# Mega_Stepper_Shield.net
KiCad netlist of a schematic drawn in EAGLE
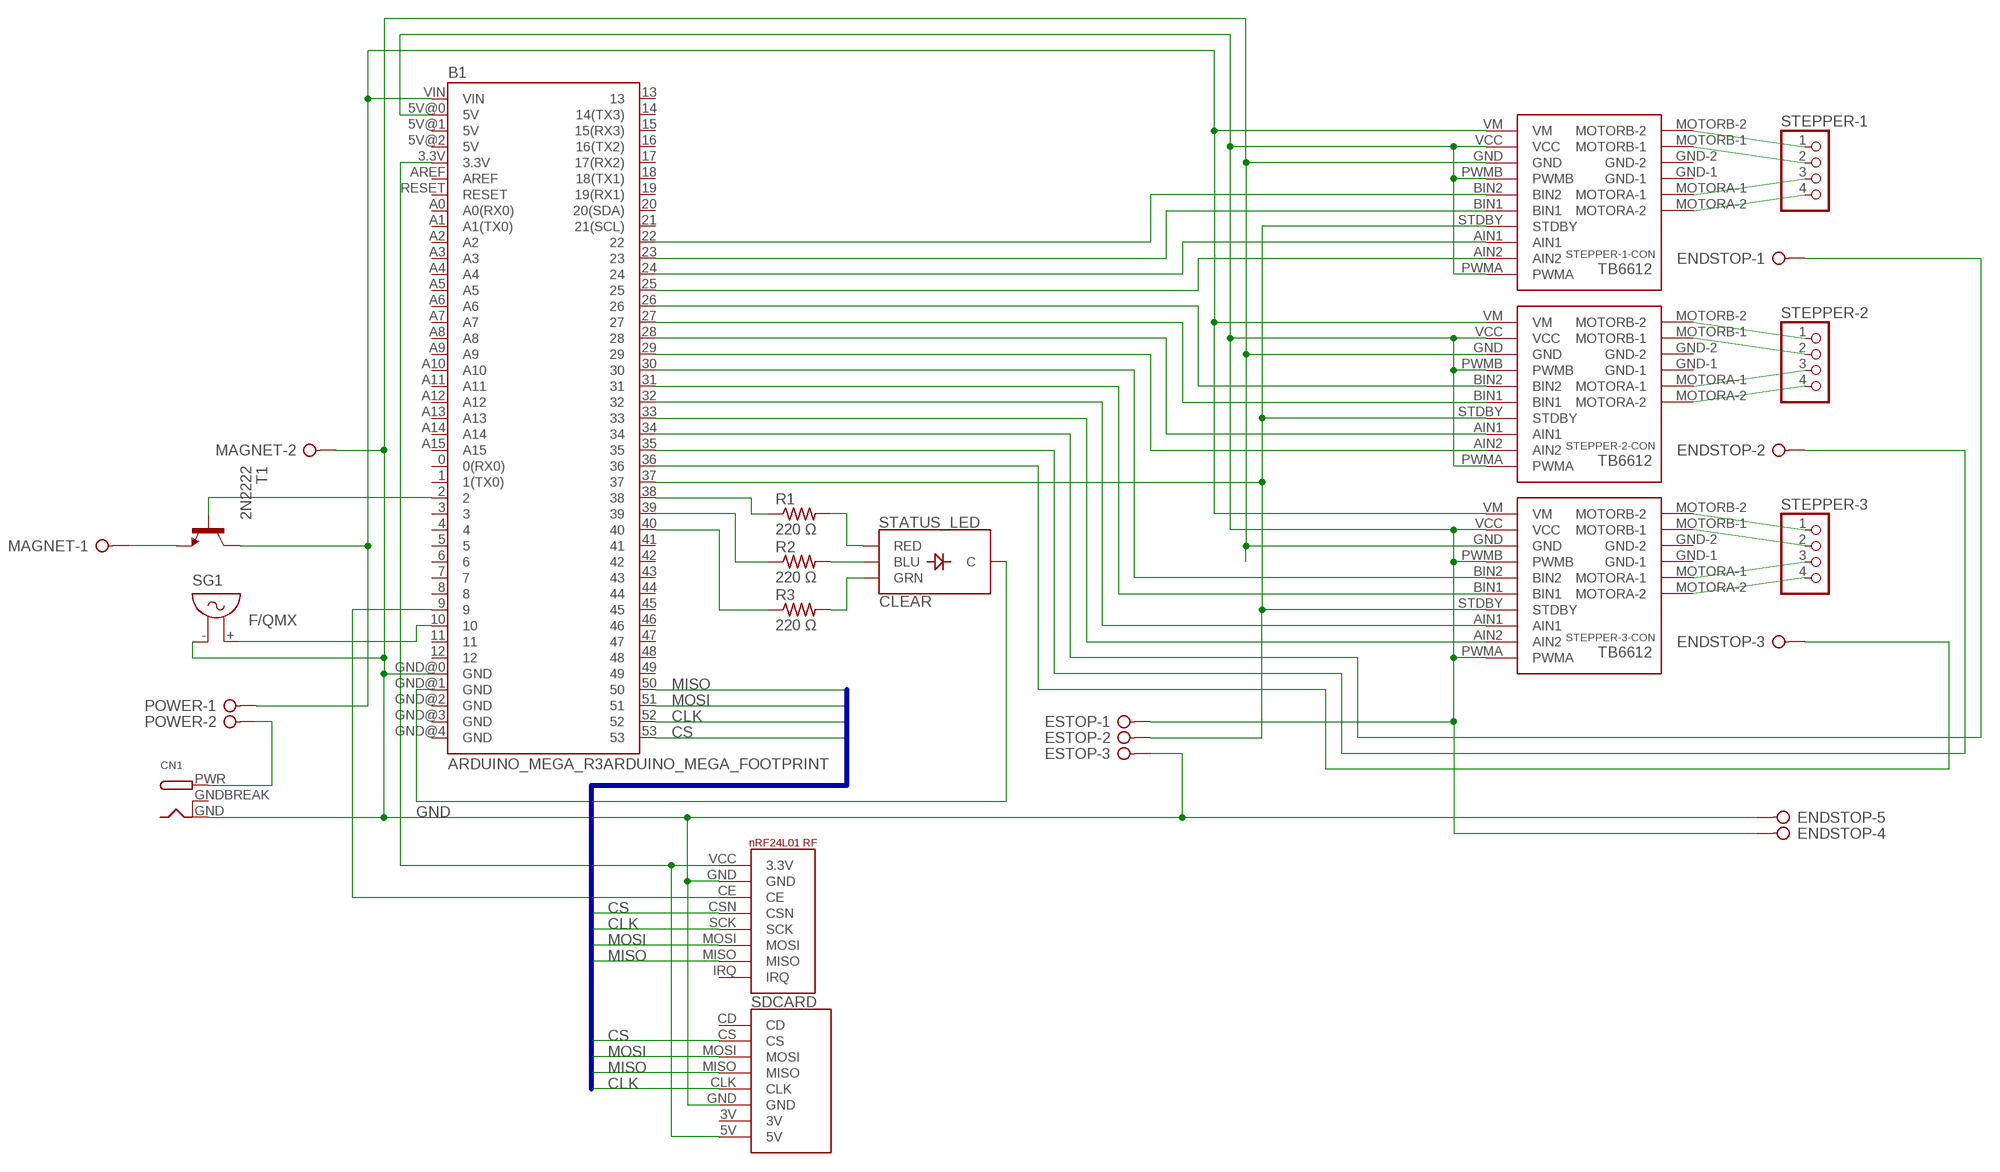
[diagram p0: schematic, sheet 1]

(export (version "E")
  (design (tool "Eeschema 10.0.6"))
  (components
    (comp (ref "B1")
      (value "ARDUINO_MEGA_R3ARDUINO_MEGA_FOOTPRINT")
      (footprint "eagle-import:ARDUINO_MEGA_SHIELD_DIMENSIONLESS")
      (libsource (lib "eagle-import") (part "ARDUINO_MEGA_R3ARDUINO_MEGA_FOOTPRINT"))
    )
    (comp (ref "CN1")
      (value "DCBARRELPTH")
      (footprint "eagle-import:DCJACK_2MM_PTH")
      (libsource (lib "eagle-import") (part "DCBARRELPTH"))
    )
    (comp (ref "ENDSTOP")
      (value "W237-05P")
      (footprint "eagle-import:W237-5P")
      (libsource (lib "eagle-import") (part "W237-05P"))
    )
    (comp (ref "ESTOP")
      (value "W237-3E")
      (footprint "eagle-import:W237-3E")
      (libsource (lib "eagle-import") (part "W237-3E"))
    )
    (comp (ref "MAGNET")
      (value "W237-02P")
      (footprint "eagle-import:W237-132")
      (libsource (lib "eagle-import") (part "W237-02P"))
    )
    (comp (ref "POWER")
      (value "W237-02P")
      (footprint "eagle-import:W237-132")
      (libsource (lib "eagle-import") (part "W237-02P"))
    )
    (comp (ref "R1")
      (value "220 Ω")
      (footprint "eagle-import:0204_7")
      (libsource (lib "eagle-import") (part "R-US_0204/7"))
    )
    (comp (ref "R2")
      (value "220 Ω")
      (footprint "eagle-import:0204_7")
      (libsource (lib "eagle-import") (part "R-US_0204/7"))
    )
    (comp (ref "R3")
      (value "220 Ω")
      (footprint "eagle-import:0204_7")
      (libsource (lib "eagle-import") (part "R-US_0204/7"))
    )
    (comp (ref "SDCARD")
      (value "MICRO_SD_BREAKOUT")
      (footprint "eagle-import:MICROSDCARDBREAKOUT")
      (libsource (lib "eagle-import") (part "MICRO_SD_BREAKOUT"))
    )
    (comp (ref "SG1")
      (value "F/QMX")
      (footprint "eagle-import:F_QMX")
      (libsource (lib "eagle-import") (part "F/QMX"))
    )
    (comp (ref "STATUS_LED")
      (value "CLEAR")
      (footprint "eagle-import:LED-RGB-THRU")
      (libsource (lib "eagle-import") (part "LED-RGB-CCCLEAR"))
    )
    (comp (ref "STEPPER-1")
      (value "PINHD-1X4")
      (footprint "eagle-import:1X04")
      (libsource (lib "eagle-import") (part "PINHD-1X4"))
    )
    (comp (ref "STEPPER-1-CON")
      (value "TB6612-BREAKOUT-MOTOR-CONTROLLER")
      (footprint "eagle-import:TB6612-HEADERS")
      (libsource (lib "eagle-import") (part "TB6612-BREAKOUT-MOTOR-CONTROLLER"))
    )
    (comp (ref "STEPPER-2")
      (value "PINHD-1X4")
      (footprint "eagle-import:1X04")
      (libsource (lib "eagle-import") (part "PINHD-1X4"))
    )
    (comp (ref "STEPPER-2-CON")
      (value "TB6612-BREAKOUT-MOTOR-CONTROLLER")
      (footprint "eagle-import:TB6612-HEADERS")
      (libsource (lib "eagle-import") (part "TB6612-BREAKOUT-MOTOR-CONTROLLER"))
    )
    (comp (ref "STEPPER-3")
      (value "PINHD-1X4")
      (footprint "eagle-import:1X04")
      (libsource (lib "eagle-import") (part "PINHD-1X4"))
    )
    (comp (ref "STEPPER-3-CON")
      (value "TB6612-BREAKOUT-MOTOR-CONTROLLER")
      (footprint "eagle-import:TB6612-HEADERS")
      (libsource (lib "eagle-import") (part "TB6612-BREAKOUT-MOTOR-CONTROLLER"))
    )
    (comp (ref "T1")
      (value "2N2222")
      (footprint "eagle-import:TO92-EBC-OVAL")
      (libsource (lib "eagle-import") (part "2N2222"))
    )
    (comp (ref "U$1")
      (value "NRF24L01_RF_MODULE")
      (footprint "eagle-import:NRF24L01RF")
      (libsource (lib "eagle-import") (part "NRF24L01_RF_MODULE"))
    )
  )
  (nets
    (net (code "1") (name "/CLK") (class "Default")
      (node (ref "B1") (pin "52") (pinfunction "52_52") (pintype "bidirectional"))
      (node (ref "SDCARD") (pin "CLK") (pinfunction "CLK_CLK") (pintype "bidirectional"))
      (node (ref "U$1") (pin "SCK") (pinfunction "SCK_SCK") (pintype "bidirectional"))
    )
    (net (code "2") (name "/CS") (class "Default")
      (node (ref "B1") (pin "53") (pinfunction "53_53") (pintype "bidirectional"))
      (node (ref "SDCARD") (pin "CS") (pinfunction "CS_CS") (pintype "bidirectional"))
      (node (ref "U$1") (pin "CSN") (pinfunction "CSN_CSN") (pintype "bidirectional"))
    )
    (net (code "3") (name "/GND") (class "Default")
      (node (ref "B1") (pin "GND@0") (pinfunction "GND_GND@0") (pintype "bidirectional"))
      (node (ref "CN1") (pin "GND") (pinfunction "GND_GND") (pintype "power_in"))
      (node (ref "ENDSTOP") (pin "5") (pinfunction "KL_5") (pintype "passive"))
      (node (ref "ESTOP") (pin "3") (pinfunction "KL_3") (pintype "passive"))
      (node (ref "MAGNET") (pin "2") (pinfunction "KL_2") (pintype "passive"))
      (node (ref "SDCARD") (pin "GND") (pinfunction "GND_GND") (pintype "bidirectional"))
      (node (ref "SG1") (pin "-") (pinfunction "1_-") (pintype "passive"))
      (node (ref "STEPPER-1-CON") (pin "GND") (pinfunction "GND_GND") (pintype "bidirectional"))
      (node (ref "STEPPER-2-CON") (pin "GND") (pinfunction "GND_GND") (pintype "bidirectional"))
      (node (ref "STEPPER-3-CON") (pin "GND") (pinfunction "GND_GND") (pintype "bidirectional"))
      (node (ref "U$1") (pin "GND") (pinfunction "GND_GND") (pintype "bidirectional"))
    )
    (net (code "4") (name "/GNDBREAK") (class "Default")
      (node (ref "CN1") (pin "GNDBREAK") (pinfunction "GNDBREAK_GNDBREAK") (pintype "power_in"))
    )
    (net (code "5") (name "/MISO") (class "Default")
      (node (ref "B1") (pin "50") (pinfunction "50_50") (pintype "bidirectional"))
      (node (ref "SDCARD") (pin "MISO") (pinfunction "MISO_MISO") (pintype "bidirectional"))
      (node (ref "U$1") (pin "MISO") (pinfunction "MISO_MISO") (pintype "bidirectional"))
    )
    (net (code "6") (name "/MOSI") (class "Default")
      (node (ref "B1") (pin "51") (pinfunction "51_51") (pintype "bidirectional"))
      (node (ref "SDCARD") (pin "MOSI") (pinfunction "MOSI_MOSI") (pintype "bidirectional"))
      (node (ref "U$1") (pin "MOSI") (pinfunction "MOSI_MOSI") (pintype "bidirectional"))
    )
    (net (code "7") (name "Net-(B1-Pad2)") (class "Default")
      (node (ref "B1") (pin "2") (pinfunction "2_2") (pintype "bidirectional"))
      (node (ref "T1") (pin "B") (pinfunction "B_B") (pintype "passive"))
    )
    (net (code "8") (name "Net-(B1-Pad9)") (class "Default")
      (node (ref "B1") (pin "9") (pinfunction "9_9") (pintype "bidirectional"))
      (node (ref "U$1") (pin "CE") (pinfunction "CE_CE") (pintype "bidirectional"))
    )
    (net (code "9") (name "Net-(B1-Pad22)") (class "Default")
      (node (ref "B1") (pin "22") (pinfunction "22_22") (pintype "bidirectional"))
      (node (ref "STEPPER-1-CON") (pin "BIN2") (pinfunction "BIN2_BIN2") (pintype "bidirectional"))
    )
    (net (code "10") (name "Net-(B1-Pad23)") (class "Default")
      (node (ref "B1") (pin "23") (pinfunction "23_23") (pintype "bidirectional"))
      (node (ref "STEPPER-1-CON") (pin "BIN1") (pinfunction "BIN1_BIN1") (pintype "bidirectional"))
    )
    (net (code "11") (name "Net-(B1-Pad24)") (class "Default")
      (node (ref "B1") (pin "24") (pinfunction "24_24") (pintype "bidirectional"))
      (node (ref "STEPPER-1-CON") (pin "AIN1") (pinfunction "AIN1_AIN1") (pintype "bidirectional"))
    )
    (net (code "12") (name "Net-(B1-Pad25)") (class "Default")
      (node (ref "B1") (pin "25") (pinfunction "25_25") (pintype "bidirectional"))
      (node (ref "STEPPER-1-CON") (pin "AIN2") (pinfunction "AIN2_AIN2") (pintype "bidirectional"))
    )
    (net (code "13") (name "Net-(B1-Pad26)") (class "Default")
      (node (ref "B1") (pin "26") (pinfunction "26_26") (pintype "bidirectional"))
      (node (ref "STEPPER-2-CON") (pin "BIN2") (pinfunction "BIN2_BIN2") (pintype "bidirectional"))
    )
    (net (code "14") (name "Net-(B1-Pad27)") (class "Default")
      (node (ref "B1") (pin "27") (pinfunction "27_27") (pintype "bidirectional"))
      (node (ref "STEPPER-2-CON") (pin "BIN1") (pinfunction "BIN1_BIN1") (pintype "bidirectional"))
    )
    (net (code "15") (name "Net-(B1-Pad28)") (class "Default")
      (node (ref "B1") (pin "28") (pinfunction "28_28") (pintype "bidirectional"))
      (node (ref "STEPPER-2-CON") (pin "AIN1") (pinfunction "AIN1_AIN1") (pintype "bidirectional"))
    )
    (net (code "16") (name "Net-(B1-Pad29)") (class "Default")
      (node (ref "B1") (pin "29") (pinfunction "29_29") (pintype "bidirectional"))
      (node (ref "STEPPER-2-CON") (pin "AIN2") (pinfunction "AIN2_AIN2") (pintype "bidirectional"))
    )
    (net (code "17") (name "Net-(B1-Pad30)") (class "Default")
      (node (ref "B1") (pin "30") (pinfunction "30_30") (pintype "bidirectional"))
      (node (ref "STEPPER-3-CON") (pin "BIN2") (pinfunction "BIN2_BIN2") (pintype "bidirectional"))
    )
    (net (code "18") (name "Net-(B1-Pad31)") (class "Default")
      (node (ref "B1") (pin "31") (pinfunction "31_31") (pintype "bidirectional"))
      (node (ref "STEPPER-3-CON") (pin "BIN1") (pinfunction "BIN1_BIN1") (pintype "bidirectional"))
    )
    (net (code "19") (name "Net-(B1-Pad32)") (class "Default")
      (node (ref "B1") (pin "32") (pinfunction "32_32") (pintype "bidirectional"))
      (node (ref "STEPPER-3-CON") (pin "AIN1") (pinfunction "AIN1_AIN1") (pintype "bidirectional"))
    )
    (net (code "20") (name "Net-(B1-Pad33)") (class "Default")
      (node (ref "B1") (pin "33") (pinfunction "33_33") (pintype "bidirectional"))
      (node (ref "STEPPER-3-CON") (pin "AIN2") (pinfunction "AIN2_AIN2") (pintype "bidirectional"))
    )
    (net (code "21") (name "Net-(B1-Pad38)") (class "Default")
      (node (ref "B1") (pin "38") (pinfunction "38_38") (pintype "bidirectional"))
      (node (ref "R1") (pin "1") (pinfunction "1_1") (pintype "passive"))
    )
    (net (code "22") (name "Net-(B1-Pad39)") (class "Default")
      (node (ref "B1") (pin "39") (pinfunction "39_39") (pintype "bidirectional"))
      (node (ref "R2") (pin "1") (pinfunction "1_1") (pintype "passive"))
    )
    (net (code "23") (name "Net-(B1-Pad40)") (class "Default")
      (node (ref "B1") (pin "40") (pinfunction "40_40") (pintype "bidirectional"))
      (node (ref "R3") (pin "1") (pinfunction "1_1") (pintype "passive"))
    )
    (net (code "24") (name "Net-(ENDSTOPA-KL)") (class "Default")
      (node (ref "B1") (pin "34") (pinfunction "34_34") (pintype "bidirectional"))
      (node (ref "ENDSTOP") (pin "1") (pinfunction "KL_1") (pintype "passive"))
    )
    (net (code "25") (name "Net-(ENDSTOPB-KL)") (class "Default")
      (node (ref "B1") (pin "35") (pinfunction "35_35") (pintype "bidirectional"))
      (node (ref "ENDSTOP") (pin "2") (pinfunction "KL_2") (pintype "passive"))
    )
    (net (code "26") (name "Net-(ENDSTOPC-KL)") (class "Default")
      (node (ref "B1") (pin "36") (pinfunction "36_36") (pintype "bidirectional"))
      (node (ref "ENDSTOP") (pin "3") (pinfunction "KL_3") (pintype "passive"))
    )
    (net (code "27") (name "Net-(ENDSTOPD-KL)") (class "Default")
      (node (ref "B1") (pin "5V@0") (pinfunction "5V_5V@0") (pintype "bidirectional"))
      (node (ref "ENDSTOP") (pin "4") (pinfunction "KL_4") (pintype "passive"))
      (node (ref "ESTOP") (pin "1") (pinfunction "KL_1") (pintype "passive"))
      (node (ref "STEPPER-1-CON") (pin "PWMA") (pinfunction "PWMA_PWMA") (pintype "bidirectional"))
      (node (ref "STEPPER-1-CON") (pin "PWMB") (pinfunction "PWMB_PWMB") (pintype "bidirectional"))
      (node (ref "STEPPER-1-CON") (pin "VCC") (pinfunction "VCC_VCC") (pintype "bidirectional"))
      (node (ref "STEPPER-2-CON") (pin "PWMA") (pinfunction "PWMA_PWMA") (pintype "bidirectional"))
      (node (ref "STEPPER-2-CON") (pin "PWMB") (pinfunction "PWMB_PWMB") (pintype "bidirectional"))
      (node (ref "STEPPER-2-CON") (pin "VCC") (pinfunction "VCC_VCC") (pintype "bidirectional"))
      (node (ref "STEPPER-3-CON") (pin "PWMA") (pinfunction "PWMA_PWMA") (pintype "bidirectional"))
      (node (ref "STEPPER-3-CON") (pin "PWMB") (pinfunction "PWMB_PWMB") (pintype "bidirectional"))
      (node (ref "STEPPER-3-CON") (pin "VCC") (pinfunction "VCC_VCC") (pintype "bidirectional"))
    )
    (net (code "28") (name "Net-(ESTOPB-KL)") (class "Default")
      (node (ref "B1") (pin "37") (pinfunction "37_37") (pintype "bidirectional"))
      (node (ref "ESTOP") (pin "2") (pinfunction "KL_2") (pintype "passive"))
      (node (ref "STEPPER-1-CON") (pin "STDBY") (pinfunction "STDBY_STDBY") (pintype "bidirectional"))
      (node (ref "STEPPER-2-CON") (pin "STDBY") (pinfunction "STDBY_STDBY") (pintype "bidirectional"))
      (node (ref "STEPPER-3-CON") (pin "STDBY") (pinfunction "STDBY_STDBY") (pintype "bidirectional"))
    )
    (net (code "29") (name "Net-(MAGNETA-KL)") (class "Default")
      (node (ref "MAGNET") (pin "1") (pinfunction "KL_1") (pintype "passive"))
      (node (ref "T1") (pin "E") (pinfunction "E_E") (pintype "passive"))
    )
    (net (code "30") (name "Net-(POWERA-KL)") (class "Default")
      (node (ref "B1") (pin "VIN") (pinfunction "VIN_VIN") (pintype "bidirectional"))
      (node (ref "POWER") (pin "1") (pinfunction "KL_1") (pintype "passive"))
      (node (ref "STEPPER-1-CON") (pin "VM") (pinfunction "VM_VM") (pintype "bidirectional"))
      (node (ref "STEPPER-2-CON") (pin "VM") (pinfunction "VM_VM") (pintype "bidirectional"))
      (node (ref "STEPPER-3-CON") (pin "VM") (pinfunction "VM_VM") (pintype "bidirectional"))
      (node (ref "T1") (pin "C") (pinfunction "C_C") (pintype "passive"))
    )
    (net (code "31") (name "Net-(POWERB-KL)") (class "Default")
      (node (ref "CN1") (pin "PWR") (pinfunction "PWR_PWR") (pintype "power_in"))
      (node (ref "POWER") (pin "2") (pinfunction "KL_2") (pintype "passive"))
    )
    (net (code "32") (name "Net-(SG1-2)") (class "Default")
      (node (ref "B1") (pin "10") (pinfunction "10_10") (pintype "bidirectional"))
      (node (ref "SG1") (pin "+") (pinfunction "2_+") (pintype "passive"))
    )
    (net (code "33") (name "Net-(STATUS_LED-BLU)") (class "Default")
      (node (ref "R2") (pin "2") (pinfunction "2_2") (pintype "passive"))
      (node (ref "STATUS_LED") (pin "4") (pinfunction "BLU_4") (pintype "bidirectional"))
    )
    (net (code "34") (name "Net-(STATUS_LED-C)") (class "Default")
      (node (ref "B1") (pin "GND@1") (pinfunction "GND_GND@1") (pintype "bidirectional"))
      (node (ref "STATUS_LED") (pin "2") (pinfunction "C_2") (pintype "bidirectional"))
    )
    (net (code "35") (name "Net-(STATUS_LED-GRN)") (class "Default")
      (node (ref "R3") (pin "2") (pinfunction "2_2") (pintype "passive"))
      (node (ref "STATUS_LED") (pin "3") (pinfunction "GRN_3") (pintype "bidirectional"))
    )
    (net (code "36") (name "Net-(STATUS_LED-RED)") (class "Default")
      (node (ref "R1") (pin "2") (pinfunction "2_2") (pintype "passive"))
      (node (ref "STATUS_LED") (pin "1") (pinfunction "RED_1") (pintype "bidirectional"))
    )
    (net (code "37") (name "Net-(STEPPER-1-CON-PadMOTORA-1)") (class "Default")
      (node (ref "STEPPER-1") (pin "3") (pinfunction "3_3") (pintype "passive"))
      (node (ref "STEPPER-1-CON") (pin "MOTORA-1") (pinfunction "MOTORA-1_MOTORA-1") (pintype "bidirectional"))
    )
    (net (code "38") (name "Net-(STEPPER-1-CON-PadMOTORA-2)") (class "Default")
      (node (ref "STEPPER-1") (pin "4") (pinfunction "4_4") (pintype "passive"))
      (node (ref "STEPPER-1-CON") (pin "MOTORA-2") (pinfunction "MOTORA-2_MOTORA-2") (pintype "bidirectional"))
    )
    (net (code "39") (name "Net-(STEPPER-1-CON-PadMOTORB-1)") (class "Default")
      (node (ref "STEPPER-1") (pin "2") (pinfunction "2_2") (pintype "passive"))
      (node (ref "STEPPER-1-CON") (pin "MOTORB-1") (pinfunction "MOTORB-1_MOTORB-1") (pintype "bidirectional"))
    )
    (net (code "40") (name "Net-(STEPPER-1-CON-PadMOTORB-2)") (class "Default")
      (node (ref "STEPPER-1") (pin "1") (pinfunction "1_1") (pintype "passive"))
      (node (ref "STEPPER-1-CON") (pin "MOTORB-2") (pinfunction "MOTORB-2_MOTORB-2") (pintype "bidirectional"))
    )
    (net (code "41") (name "Net-(STEPPER-2-CON-PadMOTORA-1)") (class "Default")
      (node (ref "STEPPER-2") (pin "3") (pinfunction "3_3") (pintype "passive"))
      (node (ref "STEPPER-2-CON") (pin "MOTORA-1") (pinfunction "MOTORA-1_MOTORA-1") (pintype "bidirectional"))
    )
    (net (code "42") (name "Net-(STEPPER-2-CON-PadMOTORA-2)") (class "Default")
      (node (ref "STEPPER-2") (pin "4") (pinfunction "4_4") (pintype "passive"))
      (node (ref "STEPPER-2-CON") (pin "MOTORA-2") (pinfunction "MOTORA-2_MOTORA-2") (pintype "bidirectional"))
    )
    (net (code "43") (name "Net-(STEPPER-2-CON-PadMOTORB-1)") (class "Default")
      (node (ref "STEPPER-2") (pin "2") (pinfunction "2_2") (pintype "passive"))
      (node (ref "STEPPER-2-CON") (pin "MOTORB-1") (pinfunction "MOTORB-1_MOTORB-1") (pintype "bidirectional"))
    )
    (net (code "44") (name "Net-(STEPPER-2-CON-PadMOTORB-2)") (class "Default")
      (node (ref "STEPPER-2") (pin "1") (pinfunction "1_1") (pintype "passive"))
      (node (ref "STEPPER-2-CON") (pin "MOTORB-2") (pinfunction "MOTORB-2_MOTORB-2") (pintype "bidirectional"))
    )
    (net (code "45") (name "Net-(STEPPER-3-CON-PadMOTORA-1)") (class "Default")
      (node (ref "STEPPER-3") (pin "3") (pinfunction "3_3") (pintype "passive"))
      (node (ref "STEPPER-3-CON") (pin "MOTORA-1") (pinfunction "MOTORA-1_MOTORA-1") (pintype "bidirectional"))
    )
    (net (code "46") (name "Net-(STEPPER-3-CON-PadMOTORA-2)") (class "Default")
      (node (ref "STEPPER-3") (pin "4") (pinfunction "4_4") (pintype "passive"))
      (node (ref "STEPPER-3-CON") (pin "MOTORA-2") (pinfunction "MOTORA-2_MOTORA-2") (pintype "bidirectional"))
    )
    (net (code "47") (name "Net-(STEPPER-3-CON-PadMOTORB-1)") (class "Default")
      (node (ref "STEPPER-3") (pin "2") (pinfunction "2_2") (pintype "passive"))
      (node (ref "STEPPER-3-CON") (pin "MOTORB-1") (pinfunction "MOTORB-1_MOTORB-1") (pintype "bidirectional"))
    )
    (net (code "48") (name "Net-(STEPPER-3-CON-PadMOTORB-2)") (class "Default")
      (node (ref "STEPPER-3") (pin "1") (pinfunction "1_1") (pintype "passive"))
      (node (ref "STEPPER-3-CON") (pin "MOTORB-2") (pinfunction "MOTORB-2_MOTORB-2") (pintype "bidirectional"))
    )
    (net (code "49") (name "Net-(U$1-3.3V)") (class "Default")
      (node (ref "B1") (pin "3.3V") (pinfunction "3.3V_3.3V") (pintype "bidirectional"))
      (node (ref "SDCARD") (pin "5V") (pinfunction "5V_5V") (pintype "bidirectional"))
      (node (ref "U$1") (pin "VCC") (pinfunction "3.3V_VCC") (pintype "bidirectional"))
    )
    (net (code "50") (name "unconnected-(B1-0(RX0)-Pad0)") (class "Default")
      (node (ref "B1") (pin "0") (pinfunction "0(RX0)_0") (pintype "bidirectional"))
    )
    (net (code "51") (name "unconnected-(B1-1(TX0)-Pad1)") (class "Default")
      (node (ref "B1") (pin "1") (pinfunction "1(TX0)_1") (pintype "bidirectional"))
    )
    (net (code "52") (name "unconnected-(B1-5V-Pad5V@1)") (class "Default")
      (node (ref "B1") (pin "5V@1") (pinfunction "5V_5V@1") (pintype "bidirectional"))
    )
    (net (code "53") (name "unconnected-(B1-5V-Pad5V@2)") (class "Default")
      (node (ref "B1") (pin "5V@2") (pinfunction "5V_5V@2") (pintype "bidirectional"))
    )
    (net (code "54") (name "unconnected-(B1-14(TX3)-Pad14)") (class "Default")
      (node (ref "B1") (pin "14") (pinfunction "14(TX3)_14") (pintype "bidirectional"))
    )
    (net (code "55") (name "unconnected-(B1-15(RX3)-Pad15)") (class "Default")
      (node (ref "B1") (pin "15") (pinfunction "15(RX3)_15") (pintype "bidirectional"))
    )
    (net (code "56") (name "unconnected-(B1-16(TX2)-Pad16)") (class "Default")
      (node (ref "B1") (pin "16") (pinfunction "16(TX2)_16") (pintype "bidirectional"))
    )
    (net (code "57") (name "unconnected-(B1-17(RX2)-Pad17)") (class "Default")
      (node (ref "B1") (pin "17") (pinfunction "17(RX2)_17") (pintype "bidirectional"))
    )
    (net (code "58") (name "unconnected-(B1-18(TX1)-Pad18)") (class "Default")
      (node (ref "B1") (pin "18") (pinfunction "18(TX1)_18") (pintype "bidirectional"))
    )
    (net (code "59") (name "unconnected-(B1-19(RX1)-Pad19)") (class "Default")
      (node (ref "B1") (pin "19") (pinfunction "19(RX1)_19") (pintype "bidirectional"))
    )
    (net (code "60") (name "unconnected-(B1-20(SDA)-Pad20)") (class "Default")
      (node (ref "B1") (pin "20") (pinfunction "20(SDA)_20") (pintype "bidirectional"))
    )
    (net (code "61") (name "unconnected-(B1-21(SCL)-Pad21)") (class "Default")
      (node (ref "B1") (pin "21") (pinfunction "21(SCL)_21") (pintype "bidirectional"))
    )
    (net (code "62") (name "unconnected-(B1-A0(RX0)-PadA0)") (class "Default")
      (node (ref "B1") (pin "A0") (pinfunction "A0(RX0)_A0") (pintype "bidirectional"))
    )
    (net (code "63") (name "unconnected-(B1-A1(TX0)-PadA1)") (class "Default")
      (node (ref "B1") (pin "A1") (pinfunction "A1(TX0)_A1") (pintype "bidirectional"))
    )
    (net (code "64") (name "unconnected-(B1-GND-PadGND@2)") (class "Default")
      (node (ref "B1") (pin "GND@2") (pinfunction "GND_GND@2") (pintype "bidirectional"))
    )
    (net (code "65") (name "unconnected-(B1-GND-PadGND@3)") (class "Default")
      (node (ref "B1") (pin "GND@3") (pinfunction "GND_GND@3") (pintype "bidirectional"))
    )
    (net (code "66") (name "unconnected-(B1-GND-PadGND@4)") (class "Default")
      (node (ref "B1") (pin "GND@4") (pinfunction "GND_GND@4") (pintype "bidirectional"))
    )
    (net (code "67") (name "unconnected-(B1-Pad3)") (class "Default")
      (node (ref "B1") (pin "3") (pinfunction "3_3") (pintype "bidirectional"))
    )
    (net (code "68") (name "unconnected-(B1-Pad4)") (class "Default")
      (node (ref "B1") (pin "4") (pinfunction "4_4") (pintype "bidirectional"))
    )
    (net (code "69") (name "unconnected-(B1-Pad5)") (class "Default")
      (node (ref "B1") (pin "5") (pinfunction "5_5") (pintype "bidirectional"))
    )
    (net (code "70") (name "unconnected-(B1-Pad6)") (class "Default")
      (node (ref "B1") (pin "6") (pinfunction "6_6") (pintype "bidirectional"))
    )
    (net (code "71") (name "unconnected-(B1-Pad7)") (class "Default")
      (node (ref "B1") (pin "7") (pinfunction "7_7") (pintype "bidirectional"))
    )
    (net (code "72") (name "unconnected-(B1-Pad8)") (class "Default")
      (node (ref "B1") (pin "8") (pinfunction "8_8") (pintype "bidirectional"))
    )
    (net (code "73") (name "unconnected-(B1-Pad11)") (class "Default")
      (node (ref "B1") (pin "11") (pinfunction "11_11") (pintype "bidirectional"))
    )
    (net (code "74") (name "unconnected-(B1-Pad12)") (class "Default")
      (node (ref "B1") (pin "12") (pinfunction "12_12") (pintype "bidirectional"))
    )
    (net (code "75") (name "unconnected-(B1-Pad13)") (class "Default")
      (node (ref "B1") (pin "13") (pinfunction "13_13") (pintype "bidirectional"))
    )
    (net (code "76") (name "unconnected-(B1-Pad41)") (class "Default")
      (node (ref "B1") (pin "41") (pinfunction "41_41") (pintype "bidirectional"))
    )
    (net (code "77") (name "unconnected-(B1-Pad42)") (class "Default")
      (node (ref "B1") (pin "42") (pinfunction "42_42") (pintype "bidirectional"))
    )
    (net (code "78") (name "unconnected-(B1-Pad43)") (class "Default")
      (node (ref "B1") (pin "43") (pinfunction "43_43") (pintype "bidirectional"))
    )
    (net (code "79") (name "unconnected-(B1-Pad44)") (class "Default")
      (node (ref "B1") (pin "44") (pinfunction "44_44") (pintype "bidirectional"))
    )
    (net (code "80") (name "unconnected-(B1-Pad45)") (class "Default")
      (node (ref "B1") (pin "45") (pinfunction "45_45") (pintype "bidirectional"))
    )
    (net (code "81") (name "unconnected-(B1-Pad46)") (class "Default")
      (node (ref "B1") (pin "46") (pinfunction "46_46") (pintype "bidirectional"))
    )
    (net (code "82") (name "unconnected-(B1-Pad47)") (class "Default")
      (node (ref "B1") (pin "47") (pinfunction "47_47") (pintype "bidirectional"))
    )
    (net (code "83") (name "unconnected-(B1-Pad48)") (class "Default")
      (node (ref "B1") (pin "48") (pinfunction "48_48") (pintype "bidirectional"))
    )
    (net (code "84") (name "unconnected-(B1-Pad49)") (class "Default")
      (node (ref "B1") (pin "49") (pinfunction "49_49") (pintype "bidirectional"))
    )
    (net (code "85") (name "unconnected-(B1-PadA2)") (class "Default")
      (node (ref "B1") (pin "A2") (pinfunction "A2_A2") (pintype "bidirectional"))
    )
    (net (code "86") (name "unconnected-(B1-PadA3)") (class "Default")
      (node (ref "B1") (pin "A3") (pinfunction "A3_A3") (pintype "bidirectional"))
    )
    (net (code "87") (name "unconnected-(B1-PadA4)") (class "Default")
      (node (ref "B1") (pin "A4") (pinfunction "A4_A4") (pintype "bidirectional"))
    )
    (net (code "88") (name "unconnected-(B1-PadA5)") (class "Default")
      (node (ref "B1") (pin "A5") (pinfunction "A5_A5") (pintype "bidirectional"))
    )
    (net (code "89") (name "unconnected-(B1-PadA6)") (class "Default")
      (node (ref "B1") (pin "A6") (pinfunction "A6_A6") (pintype "bidirectional"))
    )
    (net (code "90") (name "unconnected-(B1-PadA7)") (class "Default")
      (node (ref "B1") (pin "A7") (pinfunction "A7_A7") (pintype "bidirectional"))
    )
    (net (code "91") (name "unconnected-(B1-PadA8)") (class "Default")
      (node (ref "B1") (pin "A8") (pinfunction "A8_A8") (pintype "bidirectional"))
    )
    (net (code "92") (name "unconnected-(B1-PadA9)") (class "Default")
      (node (ref "B1") (pin "A9") (pinfunction "A9_A9") (pintype "bidirectional"))
    )
    (net (code "93") (name "unconnected-(B1-PadA10)") (class "Default")
      (node (ref "B1") (pin "A10") (pinfunction "A10_A10") (pintype "bidirectional"))
    )
    (net (code "94") (name "unconnected-(B1-PadA11)") (class "Default")
      (node (ref "B1") (pin "A11") (pinfunction "A11_A11") (pintype "bidirectional"))
    )
    (net (code "95") (name "unconnected-(B1-PadA12)") (class "Default")
      (node (ref "B1") (pin "A12") (pinfunction "A12_A12") (pintype "bidirectional"))
    )
    (net (code "96") (name "unconnected-(B1-PadA13)") (class "Default")
      (node (ref "B1") (pin "A13") (pinfunction "A13_A13") (pintype "bidirectional"))
    )
    (net (code "97") (name "unconnected-(B1-PadA14)") (class "Default")
      (node (ref "B1") (pin "A14") (pinfunction "A14_A14") (pintype "bidirectional"))
    )
    (net (code "98") (name "unconnected-(B1-PadA15)") (class "Default")
      (node (ref "B1") (pin "A15") (pinfunction "A15_A15") (pintype "bidirectional"))
    )
    (net (code "99") (name "unconnected-(B1-PadAREF)") (class "Default")
      (node (ref "B1") (pin "AREF") (pinfunction "AREF_AREF") (pintype "bidirectional"))
    )
    (net (code "100") (name "unconnected-(B1-PadRESET)") (class "Default")
      (node (ref "B1") (pin "RESET") (pinfunction "RESET_RESET") (pintype "bidirectional"))
    )
    (net (code "101") (name "unconnected-(SDCARD-Pad3V)") (class "Default")
      (node (ref "SDCARD") (pin "3V") (pinfunction "3V_3V") (pintype "bidirectional"))
    )
    (net (code "102") (name "unconnected-(SDCARD-PadCD)") (class "Default")
      (node (ref "SDCARD") (pin "CD") (pinfunction "CD_CD") (pintype "bidirectional"))
    )
    (net (code "103") (name "unconnected-(STEPPER-1-CON-PadGND-1)") (class "Default")
      (node (ref "STEPPER-1-CON") (pin "GND-1") (pinfunction "GND-1_GND-1") (pintype "bidirectional"))
    )
    (net (code "104") (name "unconnected-(STEPPER-1-CON-PadGND-2)") (class "Default")
      (node (ref "STEPPER-1-CON") (pin "GND-2") (pinfunction "GND-2_GND-2") (pintype "bidirectional"))
    )
    (net (code "105") (name "unconnected-(STEPPER-2-CON-PadGND-1)") (class "Default")
      (node (ref "STEPPER-2-CON") (pin "GND-1") (pinfunction "GND-1_GND-1") (pintype "bidirectional"))
    )
    (net (code "106") (name "unconnected-(STEPPER-2-CON-PadGND-2)") (class "Default")
      (node (ref "STEPPER-2-CON") (pin "GND-2") (pinfunction "GND-2_GND-2") (pintype "bidirectional"))
    )
    (net (code "107") (name "unconnected-(STEPPER-3-CON-PadGND-1)") (class "Default")
      (node (ref "STEPPER-3-CON") (pin "GND-1") (pinfunction "GND-1_GND-1") (pintype "bidirectional"))
    )
    (net (code "108") (name "unconnected-(STEPPER-3-CON-PadGND-2)") (class "Default")
      (node (ref "STEPPER-3-CON") (pin "GND-2") (pinfunction "GND-2_GND-2") (pintype "bidirectional"))
    )
    (net (code "109") (name "unconnected-(U$1-PadIRQ)") (class "Default")
      (node (ref "U$1") (pin "IRQ") (pinfunction "IRQ_IRQ") (pintype "bidirectional"))
    )
  )
)
